# RelayDriverShield8.net
KiCad netlist of a schematic drawn in EAGLE
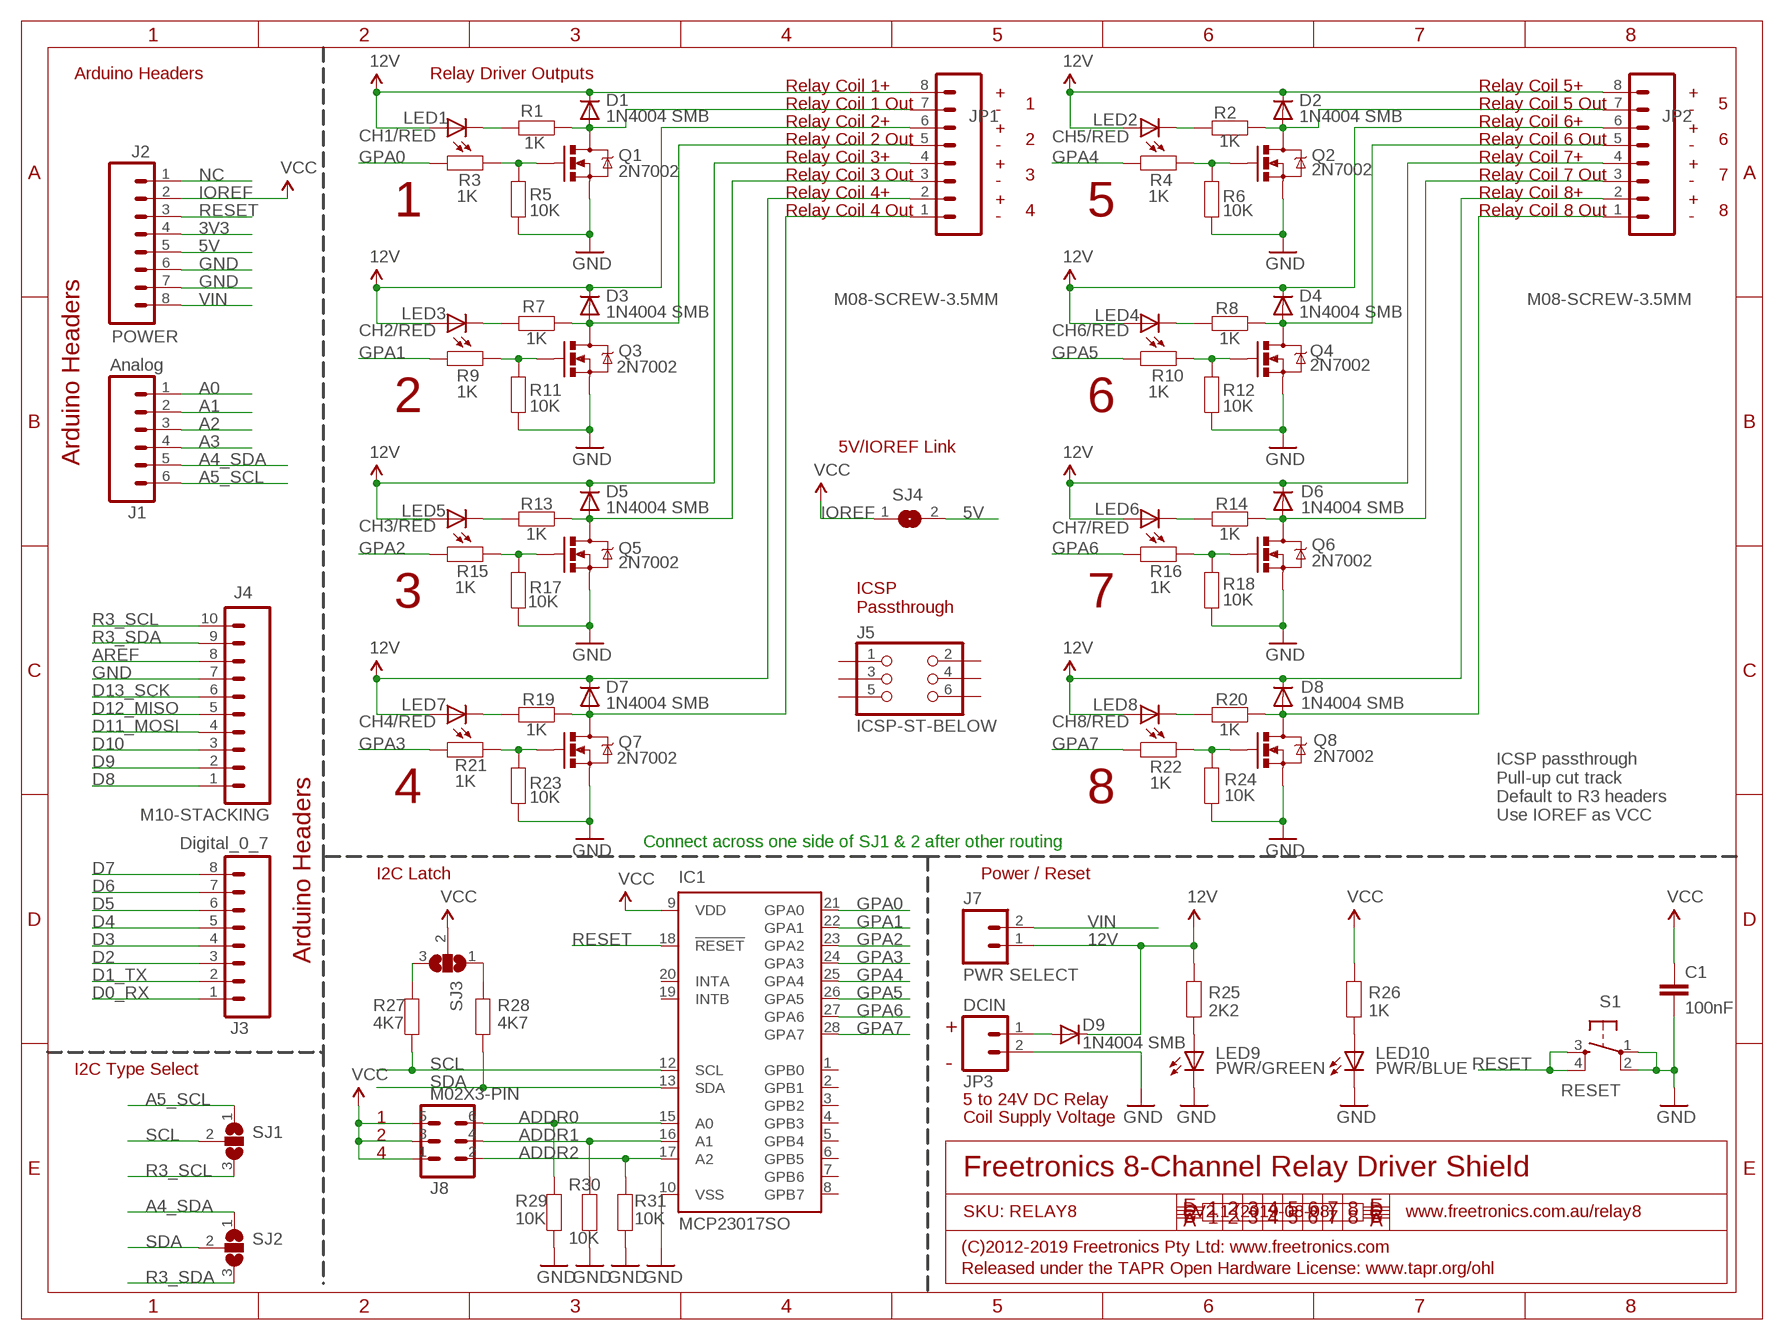
[diagram p0: schematic, sheet 1]

(export (version "E")
  (design (tool "Eeschema 10.0.6"))
  (components
    (comp (ref "C1")
      (value "100nF")
      (footprint "eagle-import:C0603")
      (libsource (lib "eagle-import") (part "CAP0603"))
    )
    (comp (ref "D1")
      (value "1N4004 SMB")
      (footprint "eagle-import:SMA-DIODE")
      (libsource (lib "eagle-import") (part "DIODESMA"))
    )
    (comp (ref "D2")
      (value "1N4004 SMB")
      (footprint "eagle-import:SMA-DIODE")
      (libsource (lib "eagle-import") (part "DIODESMA"))
    )
    (comp (ref "D3")
      (value "1N4004 SMB")
      (footprint "eagle-import:SMA-DIODE")
      (libsource (lib "eagle-import") (part "DIODESMA"))
    )
    (comp (ref "D4")
      (value "1N4004 SMB")
      (footprint "eagle-import:SMA-DIODE")
      (libsource (lib "eagle-import") (part "DIODESMA"))
    )
    (comp (ref "D5")
      (value "1N4004 SMB")
      (footprint "eagle-import:SMA-DIODE")
      (libsource (lib "eagle-import") (part "DIODESMA"))
    )
    (comp (ref "D6")
      (value "1N4004 SMB")
      (footprint "eagle-import:SMA-DIODE")
      (libsource (lib "eagle-import") (part "DIODESMA"))
    )
    (comp (ref "D7")
      (value "1N4004 SMB")
      (footprint "eagle-import:SMA-DIODE")
      (libsource (lib "eagle-import") (part "DIODESMA"))
    )
    (comp (ref "D8")
      (value "1N4004 SMB")
      (footprint "eagle-import:SMA-DIODE")
      (libsource (lib "eagle-import") (part "DIODESMA"))
    )
    (comp (ref "D9")
      (value "1N4004 SMB")
      (footprint "eagle-import:SMA-DIODE")
      (libsource (lib "eagle-import") (part "DIODESMA"))
    )
    (comp (ref "IC1")
      (value "MCP23017SO")
      (footprint "eagle-import:SO28W")
      (libsource (lib "eagle-import") (part "MCP23017SO"))
    )
    (comp (ref "J1")
      (value "Analog")
      (footprint "eagle-import:1X06-ST")
      (libsource (lib "eagle-import") (part "M06-STACKING"))
    )
    (comp (ref "J2")
      (value "POWER")
      (footprint "eagle-import:1X08-ST")
      (libsource (lib "eagle-import") (part "M08-STACKING"))
    )
    (comp (ref "J3")
      (value "Digital_0_7")
      (footprint "eagle-import:1X08-ST")
      (libsource (lib "eagle-import") (part "M08-STACKING"))
    )
    (comp (ref "J4")
      (value "M10-STACKING")
      (footprint "eagle-import:1X10-ST")
      (libsource (lib "eagle-import") (part "M10-STACKING"))
    )
    (comp (ref "J5")
      (value "ICSP-ST-BELOW")
      (footprint "eagle-import:2X03-ICSP-ST-BELOW")
      (libsource (lib "eagle-import") (part "ICSP-ST-BELOW"))
    )
    (comp (ref "J7")
      (value "PWR SELECT")
      (footprint "eagle-import:1X02-P")
      (libsource (lib "eagle-import") (part "M02-PIN"))
    )
    (comp (ref "J8")
      (value "M02X3-PIN")
      (footprint "eagle-import:2X03-P")
      (libsource (lib "eagle-import") (part "M02X3-PIN"))
    )
    (comp (ref "JP1")
      (value "M08-SCREW-3.5MM")
      (footprint "eagle-import:SCREWTERMINAL_3.5MM_8")
      (libsource (lib "eagle-import") (part "M08-SCREW-3.5MM"))
    )
    (comp (ref "JP2")
      (value "M08-SCREW-3.5MM")
      (footprint "eagle-import:SCREWTERMINAL_3.5MM_8")
      (libsource (lib "eagle-import") (part "M08-SCREW-3.5MM"))
    )
    (comp (ref "JP3")
      (value "DCIN")
      (footprint "eagle-import:SCREWTERMINAL-3.5MM-2")
      (libsource (lib "eagle-import") (part "M02-SCREW-3.5MM"))
    )
    (comp (ref "LED1")
      (value "CH1/RED")
      (footprint "eagle-import:LED-0603")
      (libsource (lib "eagle-import") (part "LED0603"))
    )
    (comp (ref "LED2")
      (value "CH5/RED")
      (footprint "eagle-import:LED-0603")
      (libsource (lib "eagle-import") (part "LED0603"))
    )
    (comp (ref "LED3")
      (value "CH2/RED")
      (footprint "eagle-import:LED-0603")
      (libsource (lib "eagle-import") (part "LED0603"))
    )
    (comp (ref "LED4")
      (value "CH6/RED")
      (footprint "eagle-import:LED-0603")
      (libsource (lib "eagle-import") (part "LED0603"))
    )
    (comp (ref "LED5")
      (value "CH3/RED")
      (footprint "eagle-import:LED-0603")
      (libsource (lib "eagle-import") (part "LED0603"))
    )
    (comp (ref "LED6")
      (value "CH7/RED")
      (footprint "eagle-import:LED-0603")
      (libsource (lib "eagle-import") (part "LED0603"))
    )
    (comp (ref "LED7")
      (value "CH4/RED")
      (footprint "eagle-import:LED-0603")
      (libsource (lib "eagle-import") (part "LED0603"))
    )
    (comp (ref "LED8")
      (value "CH8/RED")
      (footprint "eagle-import:LED-0603")
      (libsource (lib "eagle-import") (part "LED0603"))
    )
    (comp (ref "LED9")
      (value "PWR/GREEN")
      (footprint "eagle-import:LED-0603")
      (libsource (lib "eagle-import") (part "LED0603"))
    )
    (comp (ref "LED10")
      (value "PWR/BLUE")
      (footprint "eagle-import:LED-0603")
      (libsource (lib "eagle-import") (part "LED0603"))
    )
    (comp (ref "Q1")
      (value "2N7002")
      (footprint "eagle-import:SOT23-3")
      (libsource (lib "eagle-import") (part "MOSFET-NCHANNEL-233"))
    )
    (comp (ref "Q2")
      (value "2N7002")
      (footprint "eagle-import:SOT23-3")
      (libsource (lib "eagle-import") (part "MOSFET-NCHANNEL-233"))
    )
    (comp (ref "Q3")
      (value "2N7002")
      (footprint "eagle-import:SOT23-3")
      (libsource (lib "eagle-import") (part "MOSFET-NCHANNEL-233"))
    )
    (comp (ref "Q4")
      (value "2N7002")
      (footprint "eagle-import:SOT23-3")
      (libsource (lib "eagle-import") (part "MOSFET-NCHANNEL-233"))
    )
    (comp (ref "Q5")
      (value "2N7002")
      (footprint "eagle-import:SOT23-3")
      (libsource (lib "eagle-import") (part "MOSFET-NCHANNEL-233"))
    )
    (comp (ref "Q6")
      (value "2N7002")
      (footprint "eagle-import:SOT23-3")
      (libsource (lib "eagle-import") (part "MOSFET-NCHANNEL-233"))
    )
    (comp (ref "Q7")
      (value "2N7002")
      (footprint "eagle-import:SOT23-3")
      (libsource (lib "eagle-import") (part "MOSFET-NCHANNEL-233"))
    )
    (comp (ref "Q8")
      (value "2N7002")
      (footprint "eagle-import:SOT23-3")
      (libsource (lib "eagle-import") (part "MOSFET-NCHANNEL-233"))
    )
    (comp (ref "R1")
      (value "1K")
      (footprint "eagle-import:R0603")
      (libsource (lib "eagle-import") (part "RESISTOR0603"))
    )
    (comp (ref "R2")
      (value "1K")
      (footprint "eagle-import:R0603")
      (libsource (lib "eagle-import") (part "RESISTOR0603"))
    )
    (comp (ref "R3")
      (value "1K")
      (footprint "eagle-import:R0603")
      (libsource (lib "eagle-import") (part "RESISTOR0603"))
    )
    (comp (ref "R4")
      (value "1K")
      (footprint "eagle-import:R0603")
      (libsource (lib "eagle-import") (part "RESISTOR0603"))
    )
    (comp (ref "R5")
      (value "10K")
      (footprint "eagle-import:R0603")
      (libsource (lib "eagle-import") (part "RESISTOR0603"))
    )
    (comp (ref "R6")
      (value "10K")
      (footprint "eagle-import:R0603")
      (libsource (lib "eagle-import") (part "RESISTOR0603"))
    )
    (comp (ref "R7")
      (value "1K")
      (footprint "eagle-import:R0603")
      (libsource (lib "eagle-import") (part "RESISTOR0603"))
    )
    (comp (ref "R8")
      (value "1K")
      (footprint "eagle-import:R0603")
      (libsource (lib "eagle-import") (part "RESISTOR0603"))
    )
    (comp (ref "R9")
      (value "1K")
      (footprint "eagle-import:R0603")
      (libsource (lib "eagle-import") (part "RESISTOR0603"))
    )
    (comp (ref "R10")
      (value "1K")
      (footprint "eagle-import:R0603")
      (libsource (lib "eagle-import") (part "RESISTOR0603"))
    )
    (comp (ref "R11")
      (value "10K")
      (footprint "eagle-import:R0603")
      (libsource (lib "eagle-import") (part "RESISTOR0603"))
    )
    (comp (ref "R12")
      (value "10K")
      (footprint "eagle-import:R0603")
      (libsource (lib "eagle-import") (part "RESISTOR0603"))
    )
    (comp (ref "R13")
      (value "1K")
      (footprint "eagle-import:R0603")
      (libsource (lib "eagle-import") (part "RESISTOR0603"))
    )
    (comp (ref "R14")
      (value "1K")
      (footprint "eagle-import:R0603")
      (libsource (lib "eagle-import") (part "RESISTOR0603"))
    )
    (comp (ref "R15")
      (value "1K")
      (footprint "eagle-import:R0603")
      (libsource (lib "eagle-import") (part "RESISTOR0603"))
    )
    (comp (ref "R16")
      (value "1K")
      (footprint "eagle-import:R0603")
      (libsource (lib "eagle-import") (part "RESISTOR0603"))
    )
    (comp (ref "R17")
      (value "10K")
      (footprint "eagle-import:R0603")
      (libsource (lib "eagle-import") (part "RESISTOR0603"))
    )
    (comp (ref "R18")
      (value "10K")
      (footprint "eagle-import:R0603")
      (libsource (lib "eagle-import") (part "RESISTOR0603"))
    )
    (comp (ref "R19")
      (value "1K")
      (footprint "eagle-import:R0603")
      (libsource (lib "eagle-import") (part "RESISTOR0603"))
    )
    (comp (ref "R20")
      (value "1K")
      (footprint "eagle-import:R0603")
      (libsource (lib "eagle-import") (part "RESISTOR0603"))
    )
    (comp (ref "R21")
      (value "1K")
      (footprint "eagle-import:R0603")
      (libsource (lib "eagle-import") (part "RESISTOR0603"))
    )
    (comp (ref "R22")
      (value "1K")
      (footprint "eagle-import:R0603")
      (libsource (lib "eagle-import") (part "RESISTOR0603"))
    )
    (comp (ref "R23")
      (value "10K")
      (footprint "eagle-import:R0603")
      (libsource (lib "eagle-import") (part "RESISTOR0603"))
    )
    (comp (ref "R24")
      (value "10K")
      (footprint "eagle-import:R0603")
      (libsource (lib "eagle-import") (part "RESISTOR0603"))
    )
    (comp (ref "R25")
      (value "2K2")
      (footprint "eagle-import:R0603")
      (libsource (lib "eagle-import") (part "RESISTOR0603"))
    )
    (comp (ref "R26")
      (value "1K")
      (footprint "eagle-import:R0603")
      (libsource (lib "eagle-import") (part "RESISTOR0603"))
    )
    (comp (ref "R27")
      (value "4K7")
      (footprint "eagle-import:R0603")
      (libsource (lib "eagle-import") (part "RESISTOR0603"))
    )
    (comp (ref "R28")
      (value "4K7")
      (footprint "eagle-import:R0603")
      (libsource (lib "eagle-import") (part "RESISTOR0603"))
    )
    (comp (ref "R29")
      (value "10K")
      (footprint "eagle-import:R0603")
      (libsource (lib "eagle-import") (part "RESISTOR0603"))
    )
    (comp (ref "R30")
      (value "10K")
      (footprint "eagle-import:R0603")
      (libsource (lib "eagle-import") (part "RESISTOR0603"))
    )
    (comp (ref "R31")
      (value "10K")
      (footprint "eagle-import:R0603")
      (libsource (lib "eagle-import") (part "RESISTOR0603"))
    )
    (comp (ref "S1")
      (value "RESET")
      (footprint "eagle-import:TACTILE_SMT-6MM")
      (libsource (lib "eagle-import") (part "TAC_SWITCH-SMT-6"))
    )
    (comp (ref "SJ1")
      (value "SJ2W")
      (footprint "eagle-import:SJ_2")
      (libsource (lib "eagle-import") (part "SJ2W"))
    )
    (comp (ref "SJ2")
      (value "SJ2W")
      (footprint "eagle-import:SJ_2")
      (libsource (lib "eagle-import") (part "SJ2W"))
    )
    (comp (ref "SJ3")
      (value "SJ2W")
      (footprint "eagle-import:SJ_2")
      (libsource (lib "eagle-import") (part "SJ2W"))
    )
    (comp (ref "SJ4")
      (value "SJN")
      (footprint "eagle-import:SJ")
      (libsource (lib "eagle-import") (part "SJN"))
    )
  )
  (nets
    (net (code "1") (name "/3V3") (class "Default")
      (node (ref "J2") (pin "4") (pinfunction "4_4") (pintype "passive"))
    )
    (net (code "2") (name "/5V") (class "Default")
      (node (ref "J2") (pin "5") (pinfunction "5_5") (pintype "passive"))
      (node (ref "SJ4") (pin "2") (pinfunction "2_2") (pintype "passive"))
    )
    (net (code "3") (name "/A0") (class "Default")
      (node (ref "J1") (pin "1") (pinfunction "1_1") (pintype "passive"))
    )
    (net (code "4") (name "/A1") (class "Default")
      (node (ref "J1") (pin "2") (pinfunction "2_2") (pintype "passive"))
    )
    (net (code "5") (name "/A2") (class "Default")
      (node (ref "J1") (pin "3") (pinfunction "3_3") (pintype "passive"))
    )
    (net (code "6") (name "/A3") (class "Default")
      (node (ref "J1") (pin "4") (pinfunction "4_4") (pintype "passive"))
    )
    (net (code "7") (name "/A4_SDA") (class "Default")
      (node (ref "J1") (pin "5") (pinfunction "5_5") (pintype "passive"))
      (node (ref "SJ2") (pin "1") (pinfunction "1_1") (pintype "passive"))
    )
    (net (code "8") (name "/A5_SCL") (class "Default")
      (node (ref "J1") (pin "6") (pinfunction "6_6") (pintype "passive"))
      (node (ref "SJ1") (pin "1") (pinfunction "1_1") (pintype "passive"))
    )
    (net (code "9") (name "/ADDR0") (class "Default")
      (node (ref "IC1") (pin "15") (pinfunction "A0_15") (pintype "input"))
      (node (ref "J8") (pin "6") (pinfunction "6_6") (pintype "passive"))
      (node (ref "R29") (pin "2") (pinfunction "2_2") (pintype "passive"))
    )
    (net (code "10") (name "/ADDR1") (class "Default")
      (node (ref "IC1") (pin "16") (pinfunction "A1_16") (pintype "input"))
      (node (ref "J8") (pin "4") (pinfunction "4_4") (pintype "passive"))
      (node (ref "R30") (pin "2") (pinfunction "2_2") (pintype "passive"))
    )
    (net (code "11") (name "/ADDR2") (class "Default")
      (node (ref "IC1") (pin "17") (pinfunction "A2_17") (pintype "input"))
      (node (ref "J8") (pin "2") (pinfunction "2_2") (pintype "passive"))
      (node (ref "R31") (pin "2") (pinfunction "2_2") (pintype "passive"))
    )
    (net (code "12") (name "/AREF") (class "Default")
      (node (ref "J4") (pin "8") (pinfunction "8_8") (pintype "passive"))
    )
    (net (code "13") (name "/D0_RX") (class "Default")
      (node (ref "J3") (pin "1") (pinfunction "1_1") (pintype "passive"))
    )
    (net (code "14") (name "/D1_TX") (class "Default")
      (node (ref "J3") (pin "2") (pinfunction "2_2") (pintype "passive"))
    )
    (net (code "15") (name "/D2") (class "Default")
      (node (ref "J3") (pin "3") (pinfunction "3_3") (pintype "passive"))
    )
    (net (code "16") (name "/D3") (class "Default")
      (node (ref "J3") (pin "4") (pinfunction "4_4") (pintype "passive"))
    )
    (net (code "17") (name "/D4") (class "Default")
      (node (ref "J3") (pin "5") (pinfunction "5_5") (pintype "passive"))
    )
    (net (code "18") (name "/D5") (class "Default")
      (node (ref "J3") (pin "6") (pinfunction "6_6") (pintype "passive"))
    )
    (net (code "19") (name "/D6") (class "Default")
      (node (ref "J3") (pin "7") (pinfunction "7_7") (pintype "passive"))
    )
    (net (code "20") (name "/D7") (class "Default")
      (node (ref "J3") (pin "8") (pinfunction "8_8") (pintype "passive"))
    )
    (net (code "21") (name "/D8") (class "Default")
      (node (ref "J4") (pin "1") (pinfunction "1_1") (pintype "passive"))
    )
    (net (code "22") (name "/D9") (class "Default")
      (node (ref "J4") (pin "2") (pinfunction "2_2") (pintype "passive"))
    )
    (net (code "23") (name "/D10") (class "Default")
      (node (ref "J4") (pin "3") (pinfunction "3_3") (pintype "passive"))
    )
    (net (code "24") (name "/D11_MOSI") (class "Default")
      (node (ref "J4") (pin "4") (pinfunction "4_4") (pintype "passive"))
    )
    (net (code "25") (name "/D12_MISO") (class "Default")
      (node (ref "J4") (pin "5") (pinfunction "5_5") (pintype "passive"))
    )
    (net (code "26") (name "/D13_SCK") (class "Default")
      (node (ref "J4") (pin "6") (pinfunction "6_6") (pintype "passive"))
    )
    (net (code "27") (name "/GPA0") (class "Default")
      (node (ref "IC1") (pin "21") (pinfunction "GPA0_21") (pintype "bidirectional"))
      (node (ref "R3") (pin "2") (pinfunction "2_2") (pintype "passive"))
    )
    (net (code "28") (name "/GPA1") (class "Default")
      (node (ref "IC1") (pin "22") (pinfunction "GPA1_22") (pintype "bidirectional"))
      (node (ref "R9") (pin "2") (pinfunction "2_2") (pintype "passive"))
    )
    (net (code "29") (name "/GPA2") (class "Default")
      (node (ref "IC1") (pin "23") (pinfunction "GPA2_23") (pintype "bidirectional"))
      (node (ref "R15") (pin "2") (pinfunction "2_2") (pintype "passive"))
    )
    (net (code "30") (name "/GPA3") (class "Default")
      (node (ref "IC1") (pin "24") (pinfunction "GPA3_24") (pintype "bidirectional"))
      (node (ref "R21") (pin "2") (pinfunction "2_2") (pintype "passive"))
    )
    (net (code "31") (name "/GPA4") (class "Default")
      (node (ref "IC1") (pin "25") (pinfunction "GPA4_25") (pintype "bidirectional"))
      (node (ref "R4") (pin "2") (pinfunction "2_2") (pintype "passive"))
    )
    (net (code "32") (name "/GPA5") (class "Default")
      (node (ref "IC1") (pin "26") (pinfunction "GPA5_26") (pintype "bidirectional"))
      (node (ref "R10") (pin "2") (pinfunction "2_2") (pintype "passive"))
    )
    (net (code "33") (name "/GPA6") (class "Default")
      (node (ref "IC1") (pin "27") (pinfunction "GPA6_27") (pintype "bidirectional"))
      (node (ref "R16") (pin "2") (pinfunction "2_2") (pintype "passive"))
    )
    (net (code "34") (name "/GPA7") (class "Default")
      (node (ref "IC1") (pin "28") (pinfunction "GPA7_28") (pintype "bidirectional"))
      (node (ref "R22") (pin "2") (pinfunction "2_2") (pintype "passive"))
    )
    (net (code "35") (name "/NC") (class "Default")
      (node (ref "J2") (pin "1") (pinfunction "1_1") (pintype "passive"))
    )
    (net (code "36") (name "/R3_SCL") (class "Default")
      (node (ref "J4") (pin "10") (pinfunction "10_10") (pintype "passive"))
      (node (ref "SJ1") (pin "3") (pinfunction "3_3") (pintype "passive"))
    )
    (net (code "37") (name "/R3_SDA") (class "Default")
      (node (ref "J4") (pin "9") (pinfunction "9_9") (pintype "passive"))
      (node (ref "SJ2") (pin "3") (pinfunction "3_3") (pintype "passive"))
    )
    (net (code "38") (name "/RESET") (class "Default")
      (node (ref "IC1") (pin "18") (pinfunction "~{RESET}_18") (pintype "input"))
      (node (ref "J2") (pin "3") (pinfunction "3_3") (pintype "passive"))
      (node (ref "S1") (pin "3") (pinfunction "3_3") (pintype "passive"))
      (node (ref "S1") (pin "4") (pinfunction "4_4") (pintype "passive"))
    )
    (net (code "39") (name "/SCL") (class "Default")
      (node (ref "IC1") (pin "12") (pinfunction "SCL_12") (pintype "input"))
      (node (ref "R27") (pin "1") (pinfunction "1_1") (pintype "passive"))
      (node (ref "SJ1") (pin "2") (pinfunction "2_2") (pintype "passive"))
    )
    (net (code "40") (name "/SDA") (class "Default")
      (node (ref "IC1") (pin "13") (pinfunction "SDA_13") (pintype "bidirectional"))
      (node (ref "R28") (pin "1") (pinfunction "1_1") (pintype "passive"))
      (node (ref "SJ2") (pin "2") (pinfunction "2_2") (pintype "passive"))
    )
    (net (code "41") (name "/VIN") (class "Default")
      (node (ref "J2") (pin "8") (pinfunction "8_8") (pintype "passive"))
      (node (ref "J7") (pin "2") (pinfunction "2_2") (pintype "passive"))
    )
    (net (code "42") (name "12V") (class "Default")
      (node (ref "D1") (pin "C") (pinfunction "C_C") (pintype "passive"))
      (node (ref "D2") (pin "C") (pinfunction "C_C") (pintype "passive"))
      (node (ref "D3") (pin "C") (pinfunction "C_C") (pintype "passive"))
      (node (ref "D4") (pin "C") (pinfunction "C_C") (pintype "passive"))
      (node (ref "D5") (pin "C") (pinfunction "C_C") (pintype "passive"))
      (node (ref "D6") (pin "C") (pinfunction "C_C") (pintype "passive"))
      (node (ref "D7") (pin "C") (pinfunction "C_C") (pintype "passive"))
      (node (ref "D8") (pin "C") (pinfunction "C_C") (pintype "passive"))
      (node (ref "D9") (pin "C") (pinfunction "C_C") (pintype "passive"))
      (node (ref "J7") (pin "1") (pinfunction "1_1") (pintype "passive"))
      (node (ref "JP1") (pin "2") (pinfunction "2_2") (pintype "passive"))
      (node (ref "JP1") (pin "4") (pinfunction "4_4") (pintype "passive"))
      (node (ref "JP1") (pin "6") (pinfunction "6_6") (pintype "passive"))
      (node (ref "JP1") (pin "8") (pinfunction "8_8") (pintype "passive"))
      (node (ref "JP2") (pin "2") (pinfunction "2_2") (pintype "passive"))
      (node (ref "JP2") (pin "4") (pinfunction "4_4") (pintype "passive"))
      (node (ref "JP2") (pin "6") (pinfunction "6_6") (pintype "passive"))
      (node (ref "JP2") (pin "8") (pinfunction "8_8") (pintype "passive"))
      (node (ref "LED1") (pin "A") (pinfunction "A_A") (pintype "passive"))
      (node (ref "LED2") (pin "A") (pinfunction "A_A") (pintype "passive"))
      (node (ref "LED3") (pin "A") (pinfunction "A_A") (pintype "passive"))
      (node (ref "LED4") (pin "A") (pinfunction "A_A") (pintype "passive"))
      (node (ref "LED5") (pin "A") (pinfunction "A_A") (pintype "passive"))
      (node (ref "LED6") (pin "A") (pinfunction "A_A") (pintype "passive"))
      (node (ref "LED7") (pin "A") (pinfunction "A_A") (pintype "passive"))
      (node (ref "LED8") (pin "A") (pinfunction "A_A") (pintype "passive"))
      (node (ref "R25") (pin "2") (pinfunction "2_2") (pintype "passive"))
    )
    (net (code "43") (name "GND") (class "Default")
      (node (ref "C1") (pin "2") (pinfunction "2_2") (pintype "passive"))
      (node (ref "IC1") (pin "10") (pinfunction "VSS_10") (pintype "power_in"))
      (node (ref "J2") (pin "6") (pinfunction "6_6") (pintype "passive"))
      (node (ref "J2") (pin "7") (pinfunction "7_7") (pintype "passive"))
      (node (ref "J4") (pin "7") (pinfunction "7_7") (pintype "passive"))
      (node (ref "JP3") (pin "2") (pinfunction "2_2") (pintype "passive"))
      (node (ref "LED10") (pin "C") (pinfunction "C_C") (pintype "passive"))
      (node (ref "LED9") (pin "C") (pinfunction "C_C") (pintype "passive"))
      (node (ref "Q1") (pin "2") (pinfunction "S_2") (pintype "passive"))
      (node (ref "Q2") (pin "2") (pinfunction "S_2") (pintype "passive"))
      (node (ref "Q3") (pin "2") (pinfunction "S_2") (pintype "passive"))
      (node (ref "Q4") (pin "2") (pinfunction "S_2") (pintype "passive"))
      (node (ref "Q5") (pin "2") (pinfunction "S_2") (pintype "passive"))
      (node (ref "Q6") (pin "2") (pinfunction "S_2") (pintype "passive"))
      (node (ref "Q7") (pin "2") (pinfunction "S_2") (pintype "passive"))
      (node (ref "Q8") (pin "2") (pinfunction "S_2") (pintype "passive"))
      (node (ref "R11") (pin "1") (pinfunction "1_1") (pintype "passive"))
      (node (ref "R12") (pin "1") (pinfunction "1_1") (pintype "passive"))
      (node (ref "R17") (pin "1") (pinfunction "1_1") (pintype "passive"))
      (node (ref "R18") (pin "1") (pinfunction "1_1") (pintype "passive"))
      (node (ref "R23") (pin "1") (pinfunction "1_1") (pintype "passive"))
      (node (ref "R24") (pin "1") (pinfunction "1_1") (pintype "passive"))
      (node (ref "R29") (pin "1") (pinfunction "1_1") (pintype "passive"))
      (node (ref "R30") (pin "1") (pinfunction "1_1") (pintype "passive"))
      (node (ref "R31") (pin "1") (pinfunction "1_1") (pintype "passive"))
      (node (ref "R5") (pin "1") (pinfunction "1_1") (pintype "passive"))
      (node (ref "R6") (pin "1") (pinfunction "1_1") (pintype "passive"))
      (node (ref "S1") (pin "1") (pinfunction "1_1") (pintype "passive"))
      (node (ref "S1") (pin "2") (pinfunction "2_2") (pintype "passive"))
    )
    (net (code "44") (name "Net-(D9-PadA)") (class "Default")
      (node (ref "D9") (pin "A") (pinfunction "A_A") (pintype "passive"))
      (node (ref "JP3") (pin "1") (pinfunction "1_1") (pintype "passive"))
    )
    (net (code "45") (name "Net-(LED1-PadC)") (class "Default")
      (node (ref "LED1") (pin "C") (pinfunction "C_C") (pintype "passive"))
      (node (ref "R1") (pin "1") (pinfunction "1_1") (pintype "passive"))
    )
    (net (code "46") (name "Net-(LED2-PadC)") (class "Default")
      (node (ref "LED2") (pin "C") (pinfunction "C_C") (pintype "passive"))
      (node (ref "R2") (pin "1") (pinfunction "1_1") (pintype "passive"))
    )
    (net (code "47") (name "Net-(LED3-PadC)") (class "Default")
      (node (ref "LED3") (pin "C") (pinfunction "C_C") (pintype "passive"))
      (node (ref "R7") (pin "1") (pinfunction "1_1") (pintype "passive"))
    )
    (net (code "48") (name "Net-(LED4-PadC)") (class "Default")
      (node (ref "LED4") (pin "C") (pinfunction "C_C") (pintype "passive"))
      (node (ref "R8") (pin "1") (pinfunction "1_1") (pintype "passive"))
    )
    (net (code "49") (name "Net-(LED5-PadC)") (class "Default")
      (node (ref "LED5") (pin "C") (pinfunction "C_C") (pintype "passive"))
      (node (ref "R13") (pin "1") (pinfunction "1_1") (pintype "passive"))
    )
    (net (code "50") (name "Net-(LED6-PadC)") (class "Default")
      (node (ref "LED6") (pin "C") (pinfunction "C_C") (pintype "passive"))
      (node (ref "R14") (pin "1") (pinfunction "1_1") (pintype "passive"))
    )
    (net (code "51") (name "Net-(LED7-PadC)") (class "Default")
      (node (ref "LED7") (pin "C") (pinfunction "C_C") (pintype "passive"))
      (node (ref "R19") (pin "1") (pinfunction "1_1") (pintype "passive"))
    )
    (net (code "52") (name "Net-(LED8-PadC)") (class "Default")
      (node (ref "LED8") (pin "C") (pinfunction "C_C") (pintype "passive"))
      (node (ref "R20") (pin "1") (pinfunction "1_1") (pintype "passive"))
    )
    (net (code "53") (name "Net-(LED9-PadA)") (class "Default")
      (node (ref "LED9") (pin "A") (pinfunction "A_A") (pintype "passive"))
      (node (ref "R25") (pin "1") (pinfunction "1_1") (pintype "passive"))
    )
    (net (code "54") (name "Net-(LED10-PadA)") (class "Default")
      (node (ref "LED10") (pin "A") (pinfunction "A_A") (pintype "passive"))
      (node (ref "R26") (pin "1") (pinfunction "1_1") (pintype "passive"))
    )
    (net (code "55") (name "Net-(Q1-D)") (class "Default")
      (node (ref "D1") (pin "A") (pinfunction "A_A") (pintype "passive"))
      (node (ref "JP1") (pin "7") (pinfunction "7_7") (pintype "passive"))
      (node (ref "Q1") (pin "3") (pinfunction "D_3") (pintype "passive"))
      (node (ref "R1") (pin "2") (pinfunction "2_2") (pintype "passive"))
    )
    (net (code "56") (name "Net-(Q1-G)") (class "Default")
      (node (ref "Q1") (pin "1") (pinfunction "G_1") (pintype "passive"))
      (node (ref "R3") (pin "1") (pinfunction "1_1") (pintype "passive"))
      (node (ref "R5") (pin "2") (pinfunction "2_2") (pintype "passive"))
    )
    (net (code "57") (name "Net-(Q2-D)") (class "Default")
      (node (ref "D2") (pin "A") (pinfunction "A_A") (pintype "passive"))
      (node (ref "JP2") (pin "7") (pinfunction "7_7") (pintype "passive"))
      (node (ref "Q2") (pin "3") (pinfunction "D_3") (pintype "passive"))
      (node (ref "R2") (pin "2") (pinfunction "2_2") (pintype "passive"))
    )
    (net (code "58") (name "Net-(Q2-G)") (class "Default")
      (node (ref "Q2") (pin "1") (pinfunction "G_1") (pintype "passive"))
      (node (ref "R4") (pin "1") (pinfunction "1_1") (pintype "passive"))
      (node (ref "R6") (pin "2") (pinfunction "2_2") (pintype "passive"))
    )
    (net (code "59") (name "Net-(Q3-D)") (class "Default")
      (node (ref "D3") (pin "A") (pinfunction "A_A") (pintype "passive"))
      (node (ref "JP1") (pin "5") (pinfunction "5_5") (pintype "passive"))
      (node (ref "Q3") (pin "3") (pinfunction "D_3") (pintype "passive"))
      (node (ref "R7") (pin "2") (pinfunction "2_2") (pintype "passive"))
    )
    (net (code "60") (name "Net-(Q3-G)") (class "Default")
      (node (ref "Q3") (pin "1") (pinfunction "G_1") (pintype "passive"))
      (node (ref "R11") (pin "2") (pinfunction "2_2") (pintype "passive"))
      (node (ref "R9") (pin "1") (pinfunction "1_1") (pintype "passive"))
    )
    (net (code "61") (name "Net-(Q4-D)") (class "Default")
      (node (ref "D4") (pin "A") (pinfunction "A_A") (pintype "passive"))
      (node (ref "JP2") (pin "5") (pinfunction "5_5") (pintype "passive"))
      (node (ref "Q4") (pin "3") (pinfunction "D_3") (pintype "passive"))
      (node (ref "R8") (pin "2") (pinfunction "2_2") (pintype "passive"))
    )
    (net (code "62") (name "Net-(Q4-G)") (class "Default")
      (node (ref "Q4") (pin "1") (pinfunction "G_1") (pintype "passive"))
      (node (ref "R10") (pin "1") (pinfunction "1_1") (pintype "passive"))
      (node (ref "R12") (pin "2") (pinfunction "2_2") (pintype "passive"))
    )
    (net (code "63") (name "Net-(Q5-D)") (class "Default")
      (node (ref "D5") (pin "A") (pinfunction "A_A") (pintype "passive"))
      (node (ref "JP1") (pin "3") (pinfunction "3_3") (pintype "passive"))
      (node (ref "Q5") (pin "3") (pinfunction "D_3") (pintype "passive"))
      (node (ref "R13") (pin "2") (pinfunction "2_2") (pintype "passive"))
    )
    (net (code "64") (name "Net-(Q5-G)") (class "Default")
      (node (ref "Q5") (pin "1") (pinfunction "G_1") (pintype "passive"))
      (node (ref "R15") (pin "1") (pinfunction "1_1") (pintype "passive"))
      (node (ref "R17") (pin "2") (pinfunction "2_2") (pintype "passive"))
    )
    (net (code "65") (name "Net-(Q6-D)") (class "Default")
      (node (ref "D6") (pin "A") (pinfunction "A_A") (pintype "passive"))
      (node (ref "JP2") (pin "3") (pinfunction "3_3") (pintype "passive"))
      (node (ref "Q6") (pin "3") (pinfunction "D_3") (pintype "passive"))
      (node (ref "R14") (pin "2") (pinfunction "2_2") (pintype "passive"))
    )
    (net (code "66") (name "Net-(Q6-G)") (class "Default")
      (node (ref "Q6") (pin "1") (pinfunction "G_1") (pintype "passive"))
      (node (ref "R16") (pin "1") (pinfunction "1_1") (pintype "passive"))
      (node (ref "R18") (pin "2") (pinfunction "2_2") (pintype "passive"))
    )
    (net (code "67") (name "Net-(Q7-D)") (class "Default")
      (node (ref "D7") (pin "A") (pinfunction "A_A") (pintype "passive"))
      (node (ref "JP1") (pin "1") (pinfunction "1_1") (pintype "passive"))
      (node (ref "Q7") (pin "3") (pinfunction "D_3") (pintype "passive"))
      (node (ref "R19") (pin "2") (pinfunction "2_2") (pintype "passive"))
    )
    (net (code "68") (name "Net-(Q7-G)") (class "Default")
      (node (ref "Q7") (pin "1") (pinfunction "G_1") (pintype "passive"))
      (node (ref "R21") (pin "1") (pinfunction "1_1") (pintype "passive"))
      (node (ref "R23") (pin "2") (pinfunction "2_2") (pintype "passive"))
    )
    (net (code "69") (name "Net-(Q8-D)") (class "Default")
      (node (ref "D8") (pin "A") (pinfunction "A_A") (pintype "passive"))
      (node (ref "JP2") (pin "1") (pinfunction "1_1") (pintype "passive"))
      (node (ref "Q8") (pin "3") (pinfunction "D_3") (pintype "passive"))
      (node (ref "R20") (pin "2") (pinfunction "2_2") (pintype "passive"))
    )
    (net (code "70") (name "Net-(Q8-G)") (class "Default")
      (node (ref "Q8") (pin "1") (pinfunction "G_1") (pintype "passive"))
      (node (ref "R22") (pin "1") (pinfunction "1_1") (pintype "passive"))
      (node (ref "R24") (pin "2") (pinfunction "2_2") (pintype "passive"))
    )
    (net (code "71") (name "Net-(R27-Pad2)") (class "Default")
      (node (ref "R27") (pin "2") (pinfunction "2_2") (pintype "passive"))
      (node (ref "SJ3") (pin "3") (pinfunction "3_3") (pintype "passive"))
    )
    (net (code "72") (name "Net-(R28-Pad2)") (class "Default")
      (node (ref "R28") (pin "2") (pinfunction "2_2") (pintype "passive"))
      (node (ref "SJ3") (pin "1") (pinfunction "1_1") (pintype "passive"))
    )
    (net (code "73") (name "VCC") (class "Default")
      (node (ref "C1") (pin "1") (pinfunction "1_1") (pintype "passive"))
      (node (ref "IC1") (pin "9") (pinfunction "VDD_9") (pintype "power_in"))
      (node (ref "J2") (pin "2") (pinfunction "2_2") (pintype "passive"))
      (node (ref "J8") (pin "1") (pinfunction "1_1") (pintype "passive"))
      (node (ref "J8") (pin "3") (pinfunction "3_3") (pintype "passive"))
      (node (ref "J8") (pin "5") (pinfunction "5_5") (pintype "passive"))
      (node (ref "R26") (pin "2") (pinfunction "2_2") (pintype "passive"))
      (node (ref "SJ3") (pin "2") (pinfunction "2_2") (pintype "passive"))
      (node (ref "SJ4") (pin "1") (pinfunction "1_1") (pintype "passive"))
    )
    (net (code "74") (name "unconnected-(IC1-GPB0-Pad1)") (class "Default")
      (node (ref "IC1") (pin "1") (pinfunction "GPB0_1") (pintype "bidirectional"))
    )
    (net (code "75") (name "unconnected-(IC1-GPB1-Pad2)") (class "Default")
      (node (ref "IC1") (pin "2") (pinfunction "GPB1_2") (pintype "bidirectional"))
    )
    (net (code "76") (name "unconnected-(IC1-GPB2-Pad3)") (class "Default")
      (node (ref "IC1") (pin "3") (pinfunction "GPB2_3") (pintype "bidirectional"))
    )
    (net (code "77") (name "unconnected-(IC1-GPB3-Pad4)") (class "Default")
      (node (ref "IC1") (pin "4") (pinfunction "GPB3_4") (pintype "bidirectional"))
    )
    (net (code "78") (name "unconnected-(IC1-GPB4-Pad5)") (class "Default")
      (node (ref "IC1") (pin "5") (pinfunction "GPB4_5") (pintype "bidirectional"))
    )
    (net (code "79") (name "unconnected-(IC1-GPB5-Pad6)") (class "Default")
      (node (ref "IC1") (pin "6") (pinfunction "GPB5_6") (pintype "bidirectional"))
    )
    (net (code "80") (name "unconnected-(IC1-GPB6-Pad7)") (class "Default")
      (node (ref "IC1") (pin "7") (pinfunction "GPB6_7") (pintype "bidirectional"))
    )
    (net (code "81") (name "unconnected-(IC1-GPB7-Pad8)") (class "Default")
      (node (ref "IC1") (pin "8") (pinfunction "GPB7_8") (pintype "bidirectional"))
    )
    (net (code "82") (name "unconnected-(IC1-INTA-Pad20)") (class "Default")
      (node (ref "IC1") (pin "20") (pinfunction "INTA_20") (pintype "output"))
    )
    (net (code "83") (name "unconnected-(IC1-INTB-Pad19)") (class "Default")
      (node (ref "IC1") (pin "19") (pinfunction "INTB_19") (pintype "output"))
    )
    (net (code "84") (name "unconnected-(J5-Pad1)") (class "Default")
      (node (ref "J5") (pin "1") (pinfunction "1_1") (pintype "passive"))
    )
    (net (code "85") (name "unconnected-(J5-Pad2)") (class "Default")
      (node (ref "J5") (pin "2") (pinfunction "2_2") (pintype "passive"))
    )
    (net (code "86") (name "unconnected-(J5-Pad3)") (class "Default")
      (node (ref "J5") (pin "3") (pinfunction "3_3") (pintype "passive"))
    )
    (net (code "87") (name "unconnected-(J5-Pad4)") (class "Default")
      (node (ref "J5") (pin "4") (pinfunction "4_4") (pintype "passive"))
    )
    (net (code "88") (name "unconnected-(J5-Pad5)") (class "Default")
      (node (ref "J5") (pin "5") (pinfunction "5_5") (pintype "passive"))
    )
    (net (code "89") (name "unconnected-(J5-Pad6)") (class "Default")
      (node (ref "J5") (pin "6") (pinfunction "6_6") (pintype "passive"))
    )
  )
)
